# 1-Schematic_2-Optimised-IRT-Gr4-ColleJou.net
KiCad netlist of a schematic drawn in EasyEDA
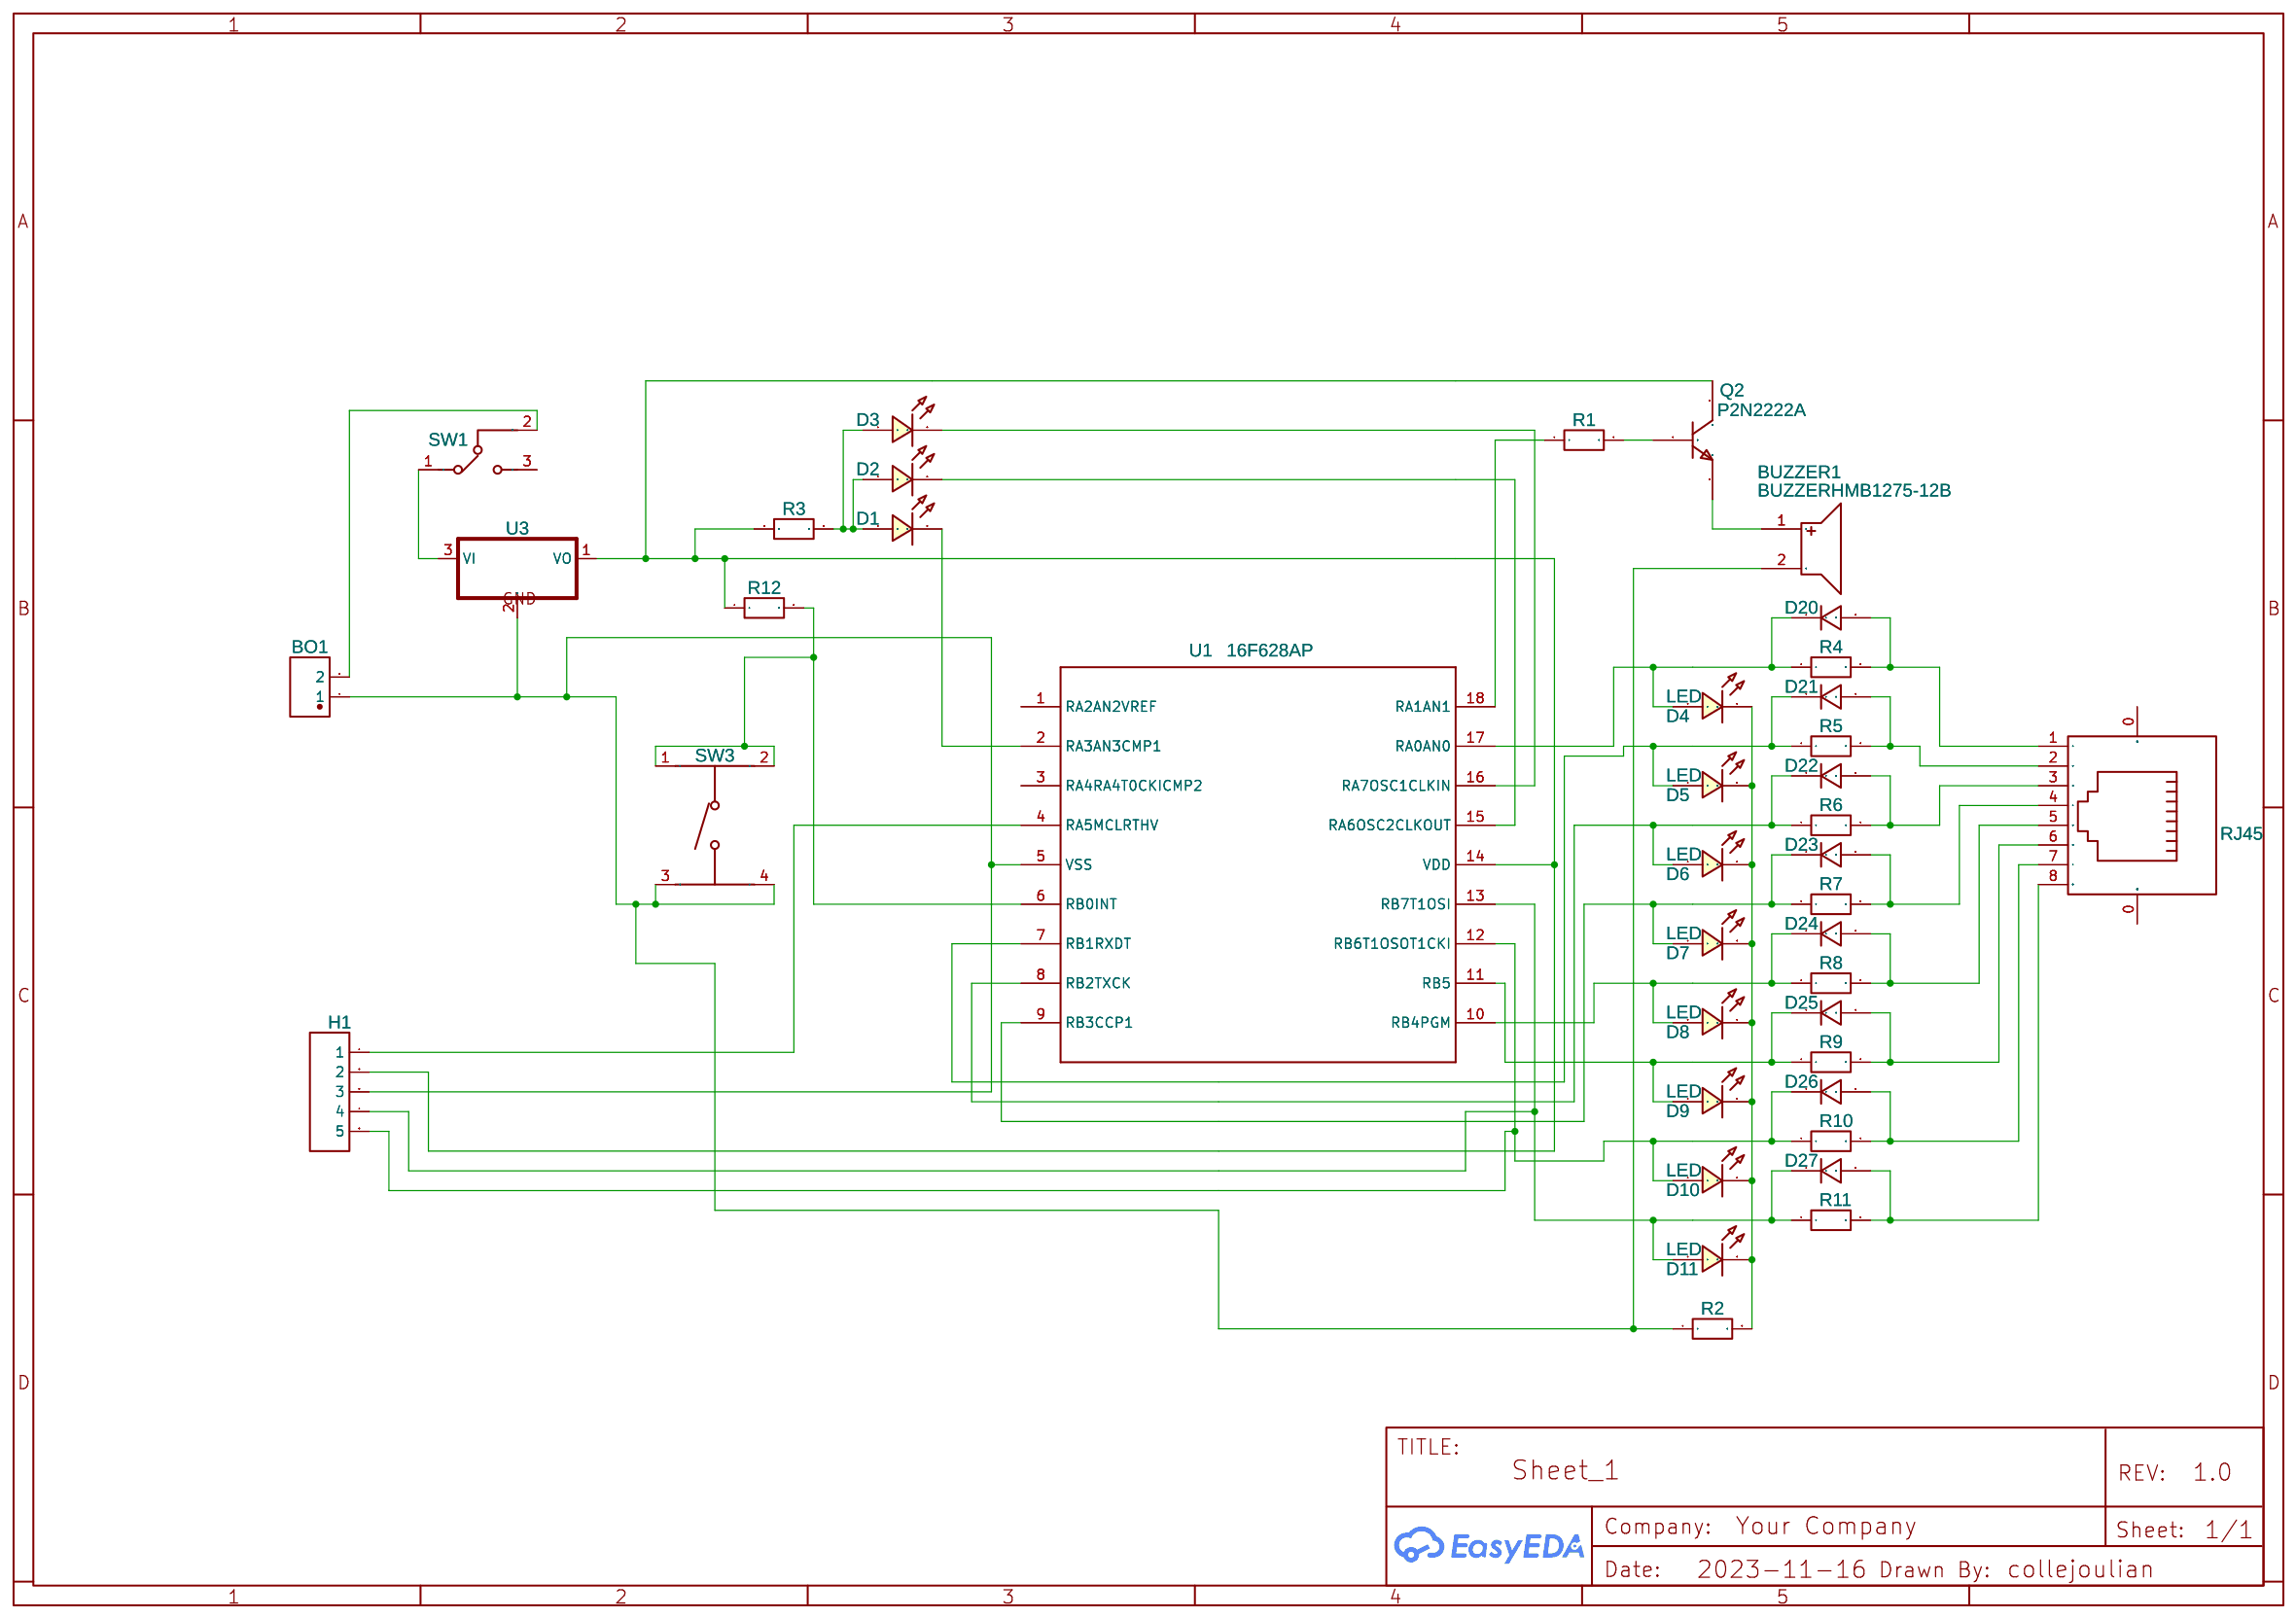
[diagram p0: schematic sheet]

(export (version "E")
  (design (tool "Eeschema 10.0.6"))
  (components
    (comp (ref "BO1")
      (value "BV-2P-5mm")
      (fields
        (field (name "Manufacturer Part") "KF301-5.0-2P")
        (field (name "Manufacturer") "Cixi Kefa Elec")
      )
      (libsource (lib "") (part "Bornier A Vis 2P - 5mm"))
    )
    (comp (ref "BUZZER1")
      (value "BUZZERHMB1275-12B")
      (fields (field (name "Manufacturer Part") "buzzerHMB1275-12B") (field (name "Manufacturer") "HNDZ"))
      (libsource (lib "") (part "BUZZERHMB1275-12B"))
    )
    (comp (ref "D1")
      (value "D1")
      (fields
        (field (name "Manufacturer Part") "204-10SDRD/S530-A3-L")
        (field (name "Manufacturer") "EVERLIGHT(台湾亿光)")
      )
      (libsource (lib "") (part "LED-TH-3mm_R"))
    )
    (comp (ref "D2")
      (value "D2")
      (fields
        (field (name "Manufacturer Part") "204-10SDRD/S530-A3-L")
        (field (name "Manufacturer") "EVERLIGHT(台湾亿光)")
      )
      (libsource (lib "") (part "LED-TH-3mm_R"))
    )
    (comp (ref "D3")
      (value "D3")
      (fields
        (field (name "Manufacturer Part") "204-10SDRD/S530-A3-L")
        (field (name "Manufacturer") "EVERLIGHT(台湾亿光)")
      )
      (libsource (lib "") (part "LED-TH-3mm_R"))
    )
    (comp (ref "D4")
      (value "LED")
      (fields
        (field (name "Manufacturer Part") "204-10SDRD/S530-A3-L")
        (field (name "Manufacturer") "EVERLIGHT(台湾亿光)")
      )
      (libsource (lib "") (part "LED-TH-3mm_R"))
    )
    (comp (ref "D5")
      (value "LED")
      (fields
        (field (name "Manufacturer Part") "204-10SDRD/S530-A3-L")
        (field (name "Manufacturer") "EVERLIGHT(台湾亿光)")
      )
      (libsource (lib "") (part "LED-TH-3mm_R"))
    )
    (comp (ref "D6")
      (value "LED")
      (fields
        (field (name "Manufacturer Part") "204-10SDRD/S530-A3-L")
        (field (name "Manufacturer") "EVERLIGHT(台湾亿光)")
      )
      (libsource (lib "") (part "LED-TH-3mm_R"))
    )
    (comp (ref "D7")
      (value "LED")
      (fields
        (field (name "Manufacturer Part") "204-10SDRD/S530-A3-L")
        (field (name "Manufacturer") "EVERLIGHT(台湾亿光)")
      )
      (libsource (lib "") (part "LED-TH-3mm_R"))
    )
    (comp (ref "D8")
      (value "LED")
      (fields
        (field (name "Manufacturer Part") "204-10SDRD/S530-A3-L")
        (field (name "Manufacturer") "EVERLIGHT(台湾亿光)")
      )
      (libsource (lib "") (part "LED-TH-3mm_R"))
    )
    (comp (ref "D9")
      (value "LED")
      (fields
        (field (name "Manufacturer Part") "204-10SDRD/S530-A3-L")
        (field (name "Manufacturer") "EVERLIGHT(台湾亿光)")
      )
      (libsource (lib "") (part "LED-TH-3mm_R"))
    )
    (comp (ref "D10")
      (value "LED")
      (fields
        (field (name "Manufacturer Part") "204-10SDRD/S530-A3-L")
        (field (name "Manufacturer") "EVERLIGHT(台湾亿光)")
      )
      (libsource (lib "") (part "LED-TH-3mm_R"))
    )
    (comp (ref "D11")
      (value "LED")
      (fields
        (field (name "Manufacturer Part") "204-10SDRD/S530-A3-L")
        (field (name "Manufacturer") "EVERLIGHT(台湾亿光)")
      )
      (libsource (lib "") (part "LED-TH-3mm_R"))
    )
    (comp (ref "D20")
      (value "D")
      (fields (field (name "Manufacturer Part") "1N4148") (field (name "Manufacturer") "STMicroelectronics"))
      (libsource (lib "") (part "1N4148"))
    )
    (comp (ref "D21")
      (value "D")
      (fields (field (name "Manufacturer Part") "1N4148") (field (name "Manufacturer") "STMicroelectronics"))
      (libsource (lib "") (part "1N4148"))
    )
    (comp (ref "D22")
      (value "D")
      (fields (field (name "Manufacturer Part") "1N4148") (field (name "Manufacturer") "STMicroelectronics"))
      (libsource (lib "") (part "1N4148"))
    )
    (comp (ref "D23")
      (value "D")
      (fields (field (name "Manufacturer Part") "1N4148") (field (name "Manufacturer") "STMicroelectronics"))
      (libsource (lib "") (part "1N4148"))
    )
    (comp (ref "D24")
      (value "D")
      (fields (field (name "Manufacturer Part") "1N4148") (field (name "Manufacturer") "STMicroelectronics"))
      (libsource (lib "") (part "1N4148"))
    )
    (comp (ref "D25")
      (value "D")
      (fields (field (name "Manufacturer Part") "1N4148") (field (name "Manufacturer") "STMicroelectronics"))
      (libsource (lib "") (part "1N4148"))
    )
    (comp (ref "D26")
      (value "D")
      (fields (field (name "Manufacturer Part") "1N4148") (field (name "Manufacturer") "STMicroelectronics"))
      (libsource (lib "") (part "1N4148"))
    )
    (comp (ref "D27")
      (value "D")
      (fields (field (name "Manufacturer Part") "1N4148") (field (name "Manufacturer") "STMicroelectronics"))
      (libsource (lib "") (part "1N4148"))
    )
    (comp (ref "H1")
      (value "1z2")
      (fields (field (name "Manufacturer Part") "2.54-1*5P母") (field (name "Manufacturer") "BOOMELE(博穆精密)"))
      (libsource (lib "") (part "Header-Female-2.54_1x5"))
    )
    (comp (ref "Q2") (value "P2N2222A") (libsource (lib "") (part "P2N2222A")))
    (comp (ref "R1") (value "1k") (libsource (lib "") (part "R_AXIAL-0.3_EU")))
    (comp (ref "R2") (value "1k") (libsource (lib "") (part "R_AXIAL-0.3_EU")))
    (comp (ref "R3") (value "1k") (libsource (lib "") (part "R_AXIAL-0.3_EU")))
    (comp (ref "R4") (value "1k") (libsource (lib "") (part "R_AXIAL-0.3_EU")))
    (comp (ref "R5") (value "1k") (libsource (lib "") (part "R_AXIAL-0.3_EU")))
    (comp (ref "R6") (value "1k") (libsource (lib "") (part "R_AXIAL-0.3_EU")))
    (comp (ref "R7") (value "1k") (libsource (lib "") (part "R_AXIAL-0.3_EU")))
    (comp (ref "R8") (value "1k") (libsource (lib "") (part "R_AXIAL-0.3_EU")))
    (comp (ref "R9") (value "1k") (libsource (lib "") (part "R_AXIAL-0.3_EU")))
    (comp (ref "R10") (value "1k") (libsource (lib "") (part "R_AXIAL-0.3_EU")))
    (comp (ref "R11") (value "1k") (libsource (lib "") (part "R_AXIAL-0.3_EU")))
    (comp (ref "R12") (value "1k") (libsource (lib "") (part "R_AXIAL-0.3_EU")))
    (comp (ref "RJ45")
      (value "RJ45")
      (fields (field (name "Manufacturer Part") "DS1128-04-S8B8P-X") (field (name "Manufacturer") "CONNFLY"))
      (libsource (lib "") (part "DS1128-04-S8B8P-X"))
    )
    (comp (ref "SW1")
      (value "SW1")
      (fields (field (name "Manufacturer Part") "1101M2S3CQE2") (field (name "Manufacturer") "C&K"))
      (libsource (lib "") (part "1101M2S3CQE2"))
    )
    (comp (ref "SW3")
      (value "TS-1102-5016")
      (fields (field (name "Manufacturer") "SOFNG(硕方)"))
      (libsource (lib "") (part "TS-1102-5016"))
    )
    (comp (ref "U1") (value "16F628AP") (libsource (lib "") (part "16F628AP")))
    (comp (ref "U3") (value "7805L") (libsource (lib "") (part "7805L")))
  )
  (nets
    (net (code "1") (name "Net-(BO1-Pad2)") (class "Default")
      (node (ref "BO1") (pin "2") (pinfunction "2_2") (pintype "unspecified"))
      (node (ref "SW1") (pin "2") (pinfunction "2_2") (pintype "unspecified"))
    )
    (net (code "2") (name "Net-(D1-Pad1)") (class "Default")
      (node (ref "D1") (pin "1") (pinfunction "1_1") (pintype "unspecified"))
      (node (ref "D2") (pin "1") (pinfunction "1_1") (pintype "unspecified"))
      (node (ref "D3") (pin "1") (pinfunction "1_1") (pintype "unspecified"))
      (node (ref "R3") (pin "2") (pinfunction "2_2") (pintype "unspecified"))
    )
    (net (code "3") (name "Net-(D10-Pad2)") (class "Default")
      (node (ref "D10") (pin "2") (pinfunction "2_2") (pintype "unspecified"))
      (node (ref "D11") (pin "2") (pinfunction "2_2") (pintype "unspecified"))
      (node (ref "D4") (pin "2") (pinfunction "2_2") (pintype "unspecified"))
      (node (ref "D5") (pin "2") (pinfunction "2_2") (pintype "unspecified"))
      (node (ref "D6") (pin "2") (pinfunction "2_2") (pintype "unspecified"))
      (node (ref "D7") (pin "2") (pinfunction "2_2") (pintype "unspecified"))
      (node (ref "D8") (pin "2") (pinfunction "2_2") (pintype "unspecified"))
      (node (ref "D9") (pin "2") (pinfunction "2_2") (pintype "unspecified"))
      (node (ref "R2") (pin "2") (pinfunction "2_2") (pintype "unspecified"))
    )
    (net (code "4") (name "Net-(D20-Pad2)") (class "Default")
      (node (ref "D20") (pin "2") (pinfunction "2_2") (pintype "unspecified"))
      (node (ref "R4") (pin "2") (pinfunction "2_2") (pintype "unspecified"))
      (node (ref "RJ45") (pin "1") (pinfunction "1_1") (pintype "unspecified"))
    )
    (net (code "5") (name "Net-(D21-Pad2)") (class "Default")
      (node (ref "D21") (pin "2") (pinfunction "2_2") (pintype "unspecified"))
      (node (ref "R5") (pin "2") (pinfunction "2_2") (pintype "unspecified"))
      (node (ref "RJ45") (pin "2") (pinfunction "2_2") (pintype "unspecified"))
    )
    (net (code "6") (name "Net-(D22-Pad2)") (class "Default")
      (node (ref "D22") (pin "2") (pinfunction "2_2") (pintype "unspecified"))
      (node (ref "R6") (pin "2") (pinfunction "2_2") (pintype "unspecified"))
      (node (ref "RJ45") (pin "3") (pinfunction "3_3") (pintype "unspecified"))
    )
    (net (code "7") (name "Net-(D23-Pad2)") (class "Default")
      (node (ref "D23") (pin "2") (pinfunction "2_2") (pintype "unspecified"))
      (node (ref "R7") (pin "2") (pinfunction "2_2") (pintype "unspecified"))
      (node (ref "RJ45") (pin "4") (pinfunction "4_4") (pintype "unspecified"))
    )
    (net (code "8") (name "Net-(D24-Pad2)") (class "Default")
      (node (ref "D24") (pin "2") (pinfunction "2_2") (pintype "unspecified"))
      (node (ref "R8") (pin "2") (pinfunction "2_2") (pintype "unspecified"))
      (node (ref "RJ45") (pin "5") (pinfunction "5_5") (pintype "unspecified"))
    )
    (net (code "9") (name "Net-(D25-Pad2)") (class "Default")
      (node (ref "D25") (pin "2") (pinfunction "2_2") (pintype "unspecified"))
      (node (ref "R9") (pin "2") (pinfunction "2_2") (pintype "unspecified"))
      (node (ref "RJ45") (pin "6") (pinfunction "6_6") (pintype "unspecified"))
    )
    (net (code "10") (name "Net-(D26-Pad2)") (class "Default")
      (node (ref "D26") (pin "2") (pinfunction "2_2") (pintype "unspecified"))
      (node (ref "R10") (pin "2") (pinfunction "2_2") (pintype "unspecified"))
      (node (ref "RJ45") (pin "7") (pinfunction "7_7") (pintype "unspecified"))
    )
    (net (code "11") (name "Net-(D27-Pad2)") (class "Default")
      (node (ref "D27") (pin "2") (pinfunction "2_2") (pintype "unspecified"))
      (node (ref "R11") (pin "2") (pinfunction "2_2") (pintype "unspecified"))
      (node (ref "RJ45") (pin "8") (pinfunction "8_8") (pintype "unspecified"))
    )
    (net (code "12") (name "Net-(Q2-B)") (class "Default")
      (node (ref "Q2") (pin "2") (pinfunction "B_2") (pintype "unspecified"))
      (node (ref "R1") (pin "2") (pinfunction "2_2") (pintype "unspecified"))
    )
    (net (code "13") (name "Net-(Q2-C)") (class "Default")
      (node (ref "H1") (pin "2") (pinfunction "2_2") (pintype "input"))
      (node (ref "Q2") (pin "1") (pinfunction "C_1") (pintype "unspecified"))
      (node (ref "R12") (pin "1") (pinfunction "1_1") (pintype "unspecified"))
      (node (ref "R3") (pin "1") (pinfunction "1_1") (pintype "unspecified"))
      (node (ref "U1") (pin "14") (pinfunction "VDD_14") (pintype "passive"))
      (node (ref "U3") (pin "1") (pinfunction "VO_1") (pintype "unspecified"))
    )
    (net (code "14") (name "Net-(Q2-E)") (class "Default")
      (node (ref "BUZZER1") (pin "1") (pinfunction "1_1") (pintype "unspecified"))
      (node (ref "Q2") (pin "3") (pinfunction "E_3") (pintype "unspecified"))
    )
    (net (code "15") (name "Net-(U1-RA0AN0)") (class "Default")
      (node (ref "D20") (pin "1") (pinfunction "1_1") (pintype "unspecified"))
      (node (ref "D4") (pin "1") (pinfunction "1_1") (pintype "unspecified"))
      (node (ref "R4") (pin "1") (pinfunction "1_1") (pintype "unspecified"))
      (node (ref "U1") (pin "17") (pinfunction "RA0AN0_17") (pintype "unspecified"))
    )
    (net (code "16") (name "Net-(U1-RA1AN1)") (class "Default")
      (node (ref "R1") (pin "1") (pinfunction "1_1") (pintype "unspecified"))
      (node (ref "U1") (pin "18") (pinfunction "RA1AN1_18") (pintype "unspecified"))
    )
    (net (code "17") (name "Net-(U1-RA3AN3CMP1)") (class "Default")
      (node (ref "D1") (pin "2") (pinfunction "2_2") (pintype "unspecified"))
      (node (ref "U1") (pin "2") (pinfunction "RA3AN3CMP1_2") (pintype "unspecified"))
    )
    (net (code "18") (name "Net-(U1-RA5MCLRTHV)") (class "Default")
      (node (ref "H1") (pin "1") (pinfunction "1_1") (pintype "input"))
      (node (ref "U1") (pin "4") (pinfunction "RA5MCLRTHV_4") (pintype "input"))
    )
    (net (code "19") (name "Net-(U1-RA6OSC2CLKOUT)") (class "Default")
      (node (ref "D2") (pin "2") (pinfunction "2_2") (pintype "unspecified"))
      (node (ref "U1") (pin "15") (pinfunction "RA6OSC2CLKOUT_15") (pintype "unspecified"))
    )
    (net (code "20") (name "Net-(U1-RA7OSC1CLKIN)") (class "Default")
      (node (ref "D3") (pin "2") (pinfunction "2_2") (pintype "unspecified"))
      (node (ref "U1") (pin "16") (pinfunction "RA7OSC1CLKIN_16") (pintype "unspecified"))
    )
    (net (code "21") (name "Net-(U1-RB0INT)") (class "Default")
      (node (ref "R12") (pin "2") (pinfunction "2_2") (pintype "unspecified"))
      (node (ref "SW3") (pin "1") (pinfunction "1_1") (pintype "unspecified"))
      (node (ref "SW3") (pin "2") (pinfunction "2_2") (pintype "unspecified"))
      (node (ref "U1") (pin "6") (pinfunction "RB0INT_6") (pintype "unspecified"))
    )
    (net (code "22") (name "Net-(U1-RB1RXDT)") (class "Default")
      (node (ref "D21") (pin "1") (pinfunction "1_1") (pintype "unspecified"))
      (node (ref "D5") (pin "1") (pinfunction "1_1") (pintype "unspecified"))
      (node (ref "R5") (pin "1") (pinfunction "1_1") (pintype "unspecified"))
      (node (ref "U1") (pin "7") (pinfunction "RB1RXDT_7") (pintype "unspecified"))
    )
    (net (code "23") (name "Net-(U1-RB2TXCK)") (class "Default")
      (node (ref "D22") (pin "1") (pinfunction "1_1") (pintype "unspecified"))
      (node (ref "D6") (pin "1") (pinfunction "1_1") (pintype "unspecified"))
      (node (ref "R6") (pin "1") (pinfunction "1_1") (pintype "unspecified"))
      (node (ref "U1") (pin "8") (pinfunction "RB2TXCK_8") (pintype "unspecified"))
    )
    (net (code "24") (name "Net-(U1-RB3CCP1)") (class "Default")
      (node (ref "D23") (pin "1") (pinfunction "1_1") (pintype "unspecified"))
      (node (ref "D7") (pin "1") (pinfunction "1_1") (pintype "unspecified"))
      (node (ref "R7") (pin "1") (pinfunction "1_1") (pintype "unspecified"))
      (node (ref "U1") (pin "9") (pinfunction "RB3CCP1_9") (pintype "unspecified"))
    )
    (net (code "25") (name "Net-(U1-RB4PGM)") (class "Default")
      (node (ref "D24") (pin "1") (pinfunction "1_1") (pintype "unspecified"))
      (node (ref "D8") (pin "1") (pinfunction "1_1") (pintype "unspecified"))
      (node (ref "R8") (pin "1") (pinfunction "1_1") (pintype "unspecified"))
      (node (ref "U1") (pin "10") (pinfunction "RB4PGM_10") (pintype "unspecified"))
    )
    (net (code "26") (name "Net-(U1-RB5)") (class "Default")
      (node (ref "D25") (pin "1") (pinfunction "1_1") (pintype "unspecified"))
      (node (ref "D9") (pin "1") (pinfunction "1_1") (pintype "unspecified"))
      (node (ref "R9") (pin "1") (pinfunction "1_1") (pintype "unspecified"))
      (node (ref "U1") (pin "11") (pinfunction "RB5_11") (pintype "unspecified"))
    )
    (net (code "27") (name "Net-(U1-RB6T1OSOT1CKI)") (class "Default")
      (node (ref "D10") (pin "1") (pinfunction "1_1") (pintype "unspecified"))
      (node (ref "D26") (pin "1") (pinfunction "1_1") (pintype "unspecified"))
      (node (ref "H1") (pin "5") (pinfunction "5_5") (pintype "input"))
      (node (ref "R10") (pin "1") (pinfunction "1_1") (pintype "unspecified"))
      (node (ref "U1") (pin "12") (pinfunction "RB6T1OSOT1CKI_12") (pintype "unspecified"))
    )
    (net (code "28") (name "Net-(U1-RB7T1OSI)") (class "Default")
      (node (ref "D11") (pin "1") (pinfunction "1_1") (pintype "unspecified"))
      (node (ref "D27") (pin "1") (pinfunction "1_1") (pintype "unspecified"))
      (node (ref "H1") (pin "4") (pinfunction "4_4") (pintype "input"))
      (node (ref "R11") (pin "1") (pinfunction "1_1") (pintype "unspecified"))
      (node (ref "U1") (pin "13") (pinfunction "RB7T1OSI_13") (pintype "unspecified"))
    )
    (net (code "29") (name "Net-(U1-VSS)") (class "Default")
      (node (ref "BO1") (pin "1") (pinfunction "1_1") (pintype "unspecified"))
      (node (ref "BUZZER1") (pin "2") (pinfunction "2_2") (pintype "unspecified"))
      (node (ref "H1") (pin "3") (pinfunction "3_3") (pintype "input"))
      (node (ref "R2") (pin "1") (pinfunction "1_1") (pintype "unspecified"))
      (node (ref "SW3") (pin "3") (pinfunction "3_3") (pintype "unspecified"))
      (node (ref "SW3") (pin "4") (pinfunction "4_4") (pintype "unspecified"))
      (node (ref "U1") (pin "5") (pinfunction "VSS_5") (pintype "passive"))
      (node (ref "U3") (pin "2") (pinfunction "GND_2") (pintype "unspecified"))
    )
    (net (code "30") (name "Net-(U3-VI)") (class "Default")
      (node (ref "SW1") (pin "1") (pinfunction "1_1") (pintype "unspecified"))
      (node (ref "U3") (pin "3") (pinfunction "VI_3") (pintype "input"))
    )
    (net (code "31") (name "unconnected-(RJ45-SHIELD-Pad0)") (class "Default")
      (node (ref "RJ45") (pin "0") (pinfunction "SHIELD_0") (pintype "unspecified"))
    )
    (net (code "32") (name "unconnected-(RJ45-SHIELD-Pad0)_1") (class "Default")
      (node (ref "RJ45") (pin "0") (pinfunction "SHIELD_0") (pintype "unspecified"))
    )
    (net (code "33") (name "unconnected-(SW1-Pad3)") (class "Default")
      (node (ref "SW1") (pin "3") (pinfunction "3_3") (pintype "unspecified"))
    )
    (net (code "34") (name "unconnected-(U1-RA2AN2VREF-Pad1)") (class "Default")
      (node (ref "U1") (pin "1") (pinfunction "RA2AN2VREF_1") (pintype "unspecified"))
    )
    (net (code "35") (name "unconnected-(U1-RA4RA4T0CKICMP2-Pad3)") (class "Default")
      (node (ref "U1") (pin "3") (pinfunction "RA4RA4T0CKICMP2_3") (pintype "unspecified"))
    )
  )
)
